# Main.net
KiCad netlist of a schematic drawn in Altium Designer
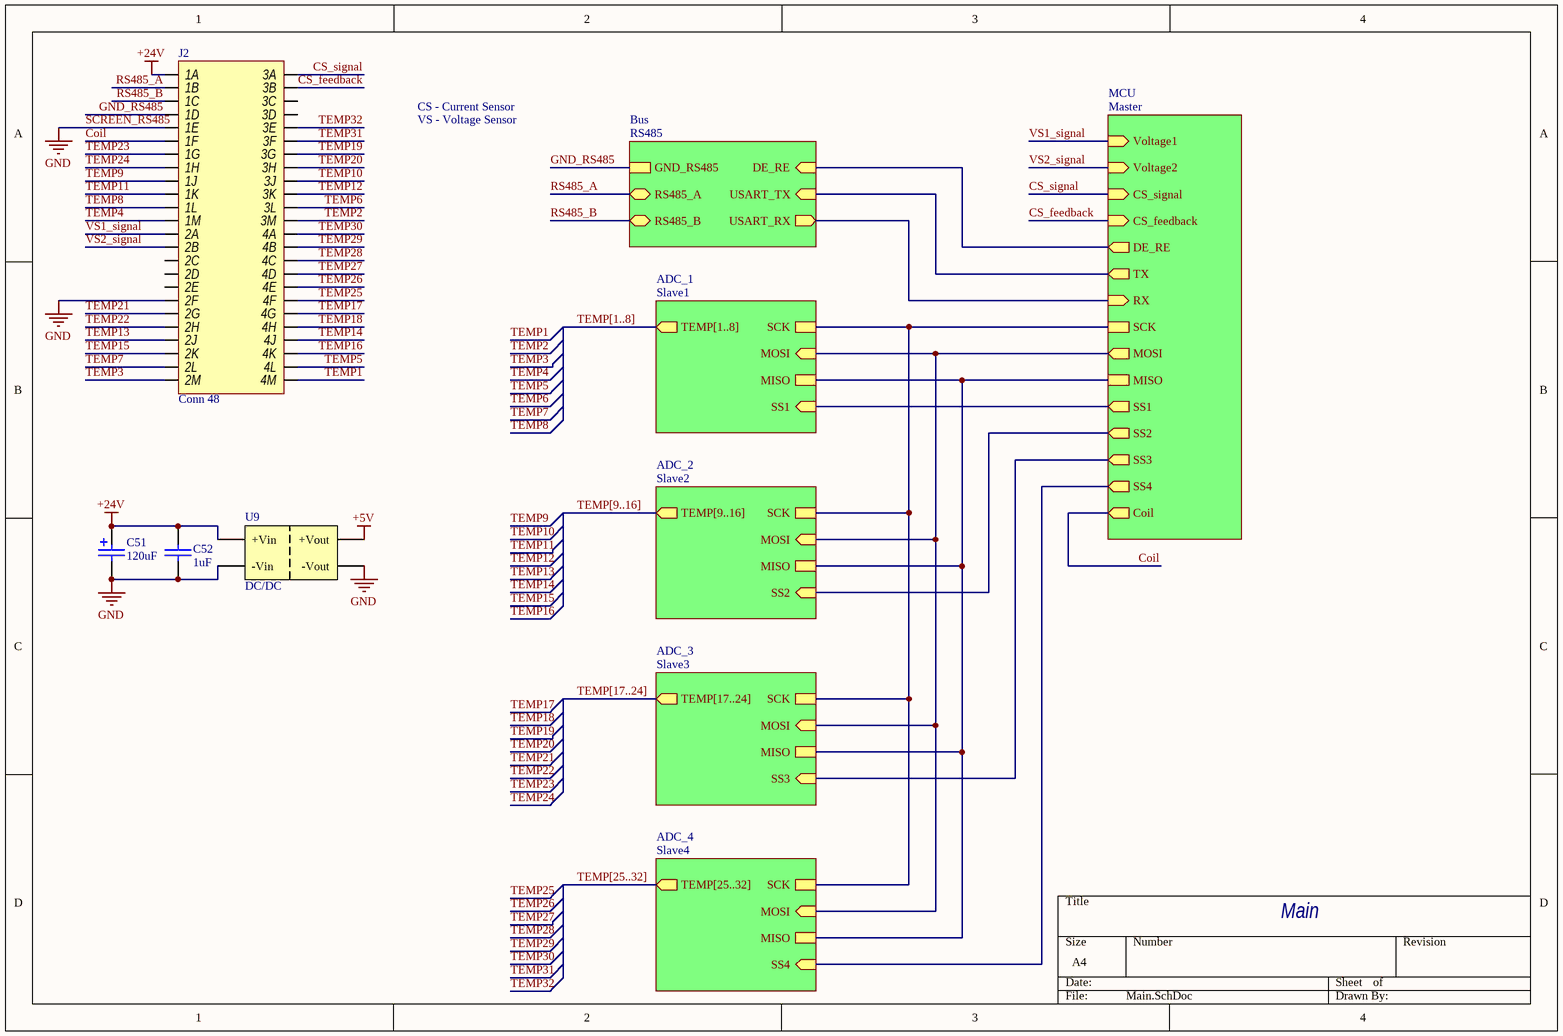
[diagram p0: Main.SchDoc]

(export (version "E")
  (design (tool "Eeschema 10.0.6"))
  (components
    (comp (ref "C51")
      (value "120uF")
      (footprint "Bar Cap 8 mm")
      (description "Polymer capacitor with low E.S.R. Rated voltage - 80V.")
      (fields (field (name "MANUFACTURER") "Matsushita") (field (name "PARTNUMBER") "EEU-FS1K121LB"))
      (libsource (lib "БУС") (part "Cap Pol 120uF"))
    )
    (comp (ref "C52")
      (value "1uF")
      (footprint "0603 Capicator")
      (description "1uF X5R 25V 10% 0603")
      (fields
        (field (name "MANUFACTURER") "Murata Manufacturing")
        (field (name "PART NUMBER") "GRM188R61E105KAADD")
      )
      (libsource (lib "БУС") (part "Cap 1uF (0603)"))
    )
    (comp (ref "J2")
      (value "Conn 48")
      (footprint "5007620481")
      (description "Molec 48 pin PCB Header 5007620481")
      (fields (field (name "MANUFACTURER") "Molex") (field (name "PART NUMBER") "5007620481"))
      (libsource (lib "БУС") (part "Conn 48 (Molex)"))
    )
    (comp (ref "U9")
      (value "DC/DC")
      (footprint "SIP7")
      (fields (field (name "MANUFACTURER") "Traco Power") (field (name "PART NUMBER") "TMH2405S"))
      (libsource (lib "БУС") (part "DC/DC Isolated 24V-5V [TMH]"))
    )
  )
  (nets
    (net (code "1") (name "+5V") (class "Default")
      (node (ref "U9") (pin "6") (pinfunction "+Vout_6") (pintype "power_in"))
    )
    (net (code "2") (name "+24V") (class "Default")
      (node (ref "C51") (pin "2") (pinfunction "2_2") (pintype "passive"))
      (node (ref "C52") (pin "2") (pinfunction "2_2") (pintype "passive"))
      (node (ref "J2") (pin "1A") (pinfunction "1A_1A") (pintype "passive"))
      (node (ref "U9") (pin "1") (pinfunction "+Vin_1") (pintype "power_in"))
    )
    (net (code "3") (name "/CS_feedback") (class "Default")
      (node (ref "J2") (pin "3B") (pinfunction "3B_3B") (pintype "passive"))
    )
    (net (code "4") (name "/CS_signal") (class "Default")
      (node (ref "J2") (pin "3A") (pinfunction "3A_3A") (pintype "passive"))
    )
    (net (code "5") (name "/Coil") (class "Default")
      (node (ref "J2") (pin "1F") (pinfunction "1F_1F") (pintype "passive"))
    )
    (net (code "7") (name "/GND_RS485") (class "Default")
      (node (ref "J2") (pin "1D") (pinfunction "1D_1D") (pintype "passive"))
    )
    (net (code "10") (name "/RS485_A") (class "Default")
      (node (ref "J2") (pin "1B") (pinfunction "1B_1B") (pintype "passive"))
    )
    (net (code "11") (name "/RS485_B") (class "Default")
      (node (ref "J2") (pin "1C") (pinfunction "1C_1C") (pintype "passive"))
    )
    (net (code "17") (name "/TEMP1") (class "Default")
      (node (ref "J2") (pin "4M") (pinfunction "4M_4M") (pintype "passive"))
    )
    (net (code "18") (name "/TEMP2") (class "Default")
      (node (ref "J2") (pin "3M") (pinfunction "3M_3M") (pintype "passive"))
    )
    (net (code "19") (name "/TEMP3") (class "Default")
      (node (ref "J2") (pin "2M") (pinfunction "2M_2M") (pintype "passive"))
    )
    (net (code "20") (name "/TEMP4") (class "Default")
      (node (ref "J2") (pin "1M") (pinfunction "1M_1M") (pintype "passive"))
    )
    (net (code "21") (name "/TEMP5") (class "Default")
      (node (ref "J2") (pin "4L") (pinfunction "4L_4L") (pintype "passive"))
    )
    (net (code "22") (name "/TEMP6") (class "Default")
      (node (ref "J2") (pin "3L") (pinfunction "3L_3L") (pintype "passive"))
    )
    (net (code "23") (name "/TEMP7") (class "Default")
      (node (ref "J2") (pin "2L") (pinfunction "2L_2L") (pintype "passive"))
    )
    (net (code "24") (name "/TEMP8") (class "Default")
      (node (ref "J2") (pin "1L") (pinfunction "1L_1L") (pintype "passive"))
    )
    (net (code "25") (name "/TEMP9") (class "Default")
      (node (ref "J2") (pin "1J") (pinfunction "1J_1J") (pintype "passive"))
    )
    (net (code "26") (name "/TEMP10") (class "Default")
      (node (ref "J2") (pin "3J") (pinfunction "3J_3J") (pintype "passive"))
    )
    (net (code "27") (name "/TEMP11") (class "Default")
      (node (ref "J2") (pin "1K") (pinfunction "1K_1K") (pintype "passive"))
    )
    (net (code "28") (name "/TEMP12") (class "Default")
      (node (ref "J2") (pin "3K") (pinfunction "3K_3K") (pintype "passive"))
    )
    (net (code "29") (name "/TEMP13") (class "Default")
      (node (ref "J2") (pin "2J") (pinfunction "2J_2J") (pintype "passive"))
    )
    (net (code "30") (name "/TEMP14") (class "Default")
      (node (ref "J2") (pin "4J") (pinfunction "4J_4J") (pintype "passive"))
    )
    (net (code "31") (name "/TEMP15") (class "Default")
      (node (ref "J2") (pin "2K") (pinfunction "2K_2K") (pintype "passive"))
    )
    (net (code "32") (name "/TEMP16") (class "Default")
      (node (ref "J2") (pin "4K") (pinfunction "4K_4K") (pintype "passive"))
    )
    (net (code "33") (name "/TEMP17") (class "Default")
      (node (ref "J2") (pin "4G") (pinfunction "4G_4G") (pintype "passive"))
    )
    (net (code "34") (name "/TEMP18") (class "Default")
      (node (ref "J2") (pin "4H") (pinfunction "4H_4H") (pintype "passive"))
    )
    (net (code "35") (name "/TEMP19") (class "Default")
      (node (ref "J2") (pin "3G") (pinfunction "3G_3G") (pintype "passive"))
    )
    (net (code "36") (name "/TEMP20") (class "Default")
      (node (ref "J2") (pin "3H") (pinfunction "3H_3H") (pintype "passive"))
    )
    (net (code "37") (name "/TEMP21") (class "Default")
      (node (ref "J2") (pin "2G") (pinfunction "2G_2G") (pintype "passive"))
    )
    (net (code "38") (name "/TEMP22") (class "Default")
      (node (ref "J2") (pin "2H") (pinfunction "2H_2H") (pintype "passive"))
    )
    (net (code "39") (name "/TEMP23") (class "Default")
      (node (ref "J2") (pin "1G") (pinfunction "1G_1G") (pintype "passive"))
    )
    (net (code "40") (name "/TEMP24") (class "Default")
      (node (ref "J2") (pin "1H") (pinfunction "1H_1H") (pintype "passive"))
    )
    (net (code "41") (name "/TEMP25") (class "Default")
      (node (ref "J2") (pin "4F") (pinfunction "4F_4F") (pintype "passive"))
    )
    (net (code "42") (name "/TEMP26") (class "Default")
      (node (ref "J2") (pin "4E") (pinfunction "4E_4E") (pintype "passive"))
    )
    (net (code "43") (name "/TEMP27") (class "Default")
      (node (ref "J2") (pin "4D") (pinfunction "4D_4D") (pintype "passive"))
    )
    (net (code "44") (name "/TEMP28") (class "Default")
      (node (ref "J2") (pin "4C") (pinfunction "4C_4C") (pintype "passive"))
    )
    (net (code "45") (name "/TEMP29") (class "Default")
      (node (ref "J2") (pin "4B") (pinfunction "4B_4B") (pintype "passive"))
    )
    (net (code "46") (name "/TEMP30") (class "Default")
      (node (ref "J2") (pin "4A") (pinfunction "4A_4A") (pintype "passive"))
    )
    (net (code "47") (name "/TEMP31") (class "Default")
      (node (ref "J2") (pin "3F") (pinfunction "3F_3F") (pintype "passive"))
    )
    (net (code "48") (name "/TEMP32") (class "Default")
      (node (ref "J2") (pin "3E") (pinfunction "3E_3E") (pintype "passive"))
    )
    (net (code "55") (name "/VS1_signal") (class "Default")
      (node (ref "J2") (pin "2A") (pinfunction "2A_2A") (pintype "passive"))
    )
    (net (code "56") (name "/VS2_signal") (class "Default")
      (node (ref "J2") (pin "2B") (pinfunction "2B_2B") (pintype "passive"))
    )
    (net (code "57") (name "GND") (class "Default")
      (node (ref "C51") (pin "1") (pinfunction "1_1") (pintype "passive"))
      (node (ref "C52") (pin "1") (pinfunction "1_1") (pintype "passive"))
      (node (ref "J2") (pin "1E") (pinfunction "1E_1E") (pintype "passive"))
      (node (ref "J2") (pin "2F") (pinfunction "2F_2F") (pintype "passive"))
      (node (ref "U9") (pin "2") (pinfunction "-Vin_2") (pintype "power_in"))
      (node (ref "U9") (pin "4") (pinfunction "-Vout_4") (pintype "power_in"))
    )
    (net (code "58") (name "unconnected-(J2-Pad2C)") (class "Default")
      (node (ref "J2") (pin "2C") (pinfunction "2C_2C") (pintype "passive"))
    )
    (net (code "59") (name "unconnected-(J2-Pad2D)") (class "Default")
      (node (ref "J2") (pin "2D") (pinfunction "2D_2D") (pintype "passive"))
    )
    (net (code "60") (name "unconnected-(J2-Pad2E)") (class "Default")
      (node (ref "J2") (pin "2E") (pinfunction "2E_2E") (pintype "passive"))
    )
    (net (code "61") (name "unconnected-(J2-Pad3C)") (class "Default")
      (node (ref "J2") (pin "3C") (pinfunction "3C_3C") (pintype "passive"))
    )
    (net (code "62") (name "unconnected-(J2-Pad3D)") (class "Default")
      (node (ref "J2") (pin "3D") (pinfunction "3D_3D") (pintype "passive"))
    )
  )
)
